# programmer.net
KiCad netlist of a schematic drawn in Altium Designer
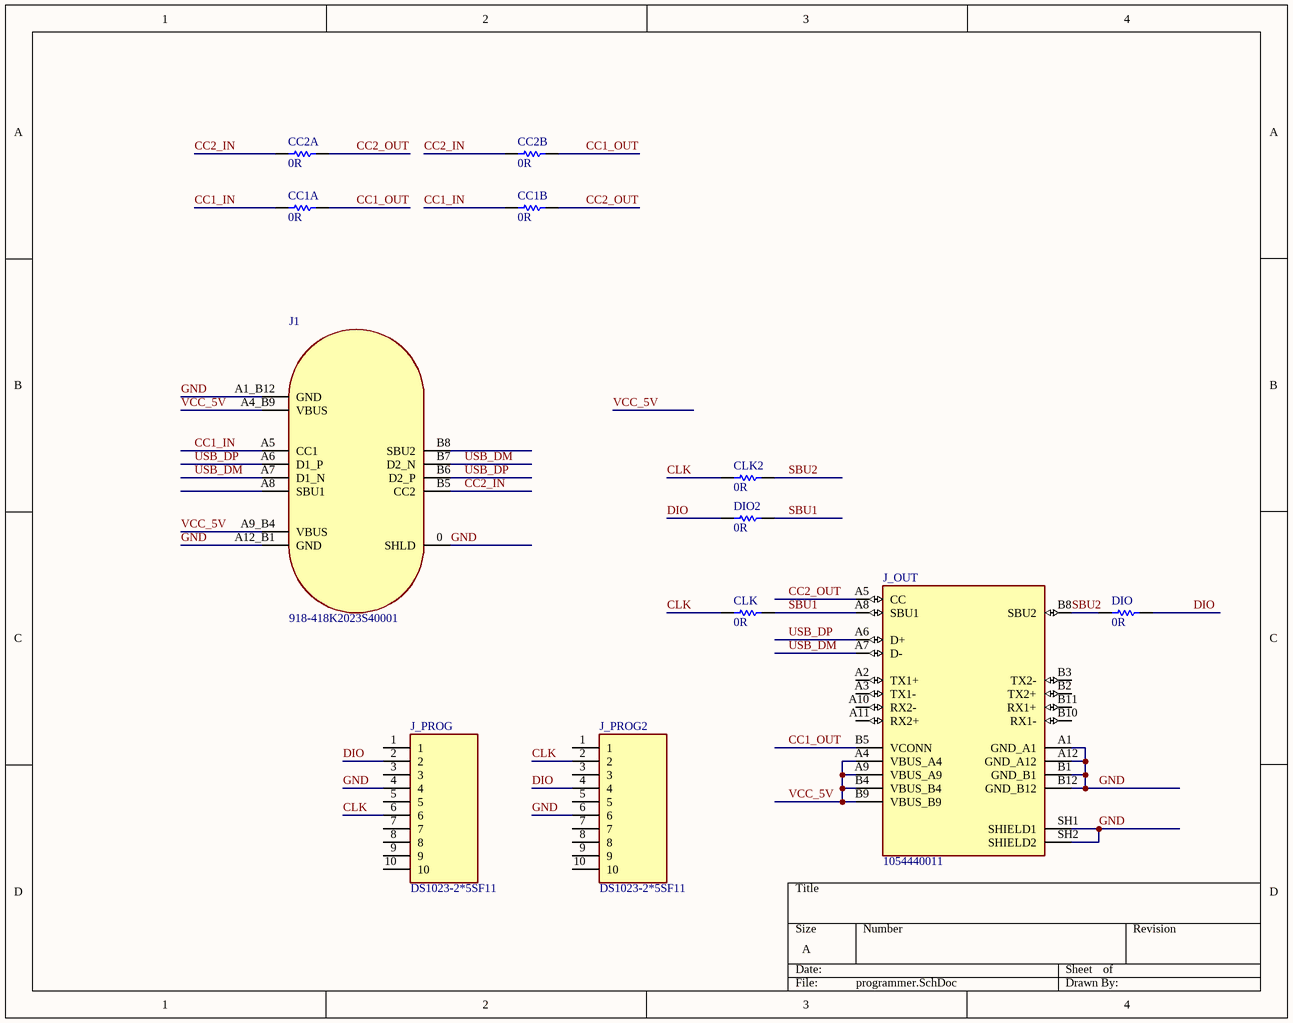
[diagram p0: programmer.SchDoc]

(export (version "E")
  (design (tool "Eeschema 10.0.6"))
  (components
    (comp (ref "CC1A")
      (value "0R")
      (footprint "R_0402")
      (description "R - RESISTOR - SMD - 0R - 1% - 0402")
      (fields (field (name "LCSC PART #") "C17168") (field (name "Comment") "0402WGF0000TCE"))
      (libsource (lib "JLC_PCB") (part "0402WGF0000TCE"))
    )
    (comp (ref "CC1B")
      (value "0R")
      (footprint "R_0402")
      (description "R - RESISTOR - SMD - 0R - 1% - 0402")
      (fields (field (name "LCSC PART #") "C17168") (field (name "Comment") "0402WGF0000TCE"))
      (libsource (lib "JLC_PCB") (part "0402WGF0000TCE"))
    )
    (comp (ref "CC2A")
      (value "0R")
      (footprint "R_0402")
      (description "R - RESISTOR - SMD - 0R - 1% - 0402")
      (fields (field (name "LCSC PART #") "C17168") (field (name "Comment") "0402WGF0000TCE"))
      (libsource (lib "JLC_PCB") (part "0402WGF0000TCE"))
    )
    (comp (ref "CC2B")
      (value "0R")
      (footprint "R_0402")
      (description "R - RESISTOR - SMD - 0R - 1% - 0402")
      (fields (field (name "LCSC PART #") "C17168") (field (name "Comment") "0402WGF0000TCE"))
      (libsource (lib "JLC_PCB") (part "0402WGF0000TCE"))
    )
    (comp (ref "CLK")
      (value "0R")
      (footprint "R_0402")
      (description "R - RESISTOR - SMD - 0R - 1% - 0402")
      (fields (field (name "LCSC PART #") "C17168") (field (name "Comment") "0402WGF0000TCE"))
      (libsource (lib "JLC_PCB") (part "0402WGF0000TCE"))
    )
    (comp (ref "CLK2")
      (value "0R")
      (footprint "R_0402")
      (description "R - RESISTOR - SMD - 0R - 1% - 0402")
      (fields (field (name "LCSC PART #") "C17168") (field (name "Comment") "0402WGF0000TCE"))
      (libsource (lib "JLC_PCB") (part "0402WGF0000TCE"))
    )
    (comp (ref "DIO")
      (value "0R")
      (footprint "R_0402")
      (description "R - RESISTOR - SMD - 0R - 1% - 0402")
      (fields (field (name "LCSC PART #") "C17168") (field (name "Comment") "0402WGF0000TCE"))
      (libsource (lib "JLC_PCB") (part "0402WGF0000TCE"))
    )
    (comp (ref "DIO2")
      (value "0R")
      (footprint "R_0402")
      (description "R - RESISTOR - SMD - 0R - 1% - 0402")
      (fields (field (name "LCSC PART #") "C17168") (field (name "Comment") "0402WGF0000TCE"))
      (libsource (lib "JLC_PCB") (part "0402WGF0000TCE"))
    )
    (comp (ref "J1")
      (value "918-418K2023S40001")
      (footprint "918-418K2023S40001")
      (description "J - JACK - USB - Type C - Recepticle - SMT - 90°")
      (fields (field (name "LCSC PART #") "C167321"))
      (libsource (lib "JLC_PCB") (part "918-418K2023S40001"))
    )
    (comp (ref "J_OUT")
      (value "1054440011")
      (footprint "MOLEX_1054440011")
      (fields (field (name "LCSC PART #") "C561769") (field (name "MF") "Molex"))
      (libsource (lib "JLC_PCB") (part "1054440011"))
    )
    (comp (ref "J_PROG")
      (value "DS1023-2*5SF11")
      (footprint "HDR_FEM_2X5P")
      (description "J - JACK - PIN_HEADER 2X5P")
      (fields (field (name "LCSC PART #") "C92270"))
      (libsource (lib "JLC_PCB") (part "DS1023-2*5SF11"))
    )
    (comp (ref "J_PROG2")
      (value "DS1023-2*5SF11")
      (footprint "HDR_FEM_2X5P")
      (description "J - JACK - PIN_HEADER 2X5P")
      (fields (field (name "LCSC PART #") "C92270"))
      (libsource (lib "JLC_PCB") (part "DS1023-2*5SF11"))
    )
  )
  (nets
    (net (code "1") (name "/CC1_IN") (class "Default")
      (node (ref "CC1A") (pin "1") (pinfunction "1_1") (pintype "passive"))
      (node (ref "CC1B") (pin "1") (pinfunction "1_1") (pintype "passive"))
      (node (ref "J1") (pin "A5") (pinfunction "CC1_A5") (pintype "passive"))
    )
    (net (code "2") (name "/CC1_OUT") (class "Default")
      (node (ref "CC1A") (pin "2") (pinfunction "2_2") (pintype "passive"))
      (node (ref "CC2B") (pin "2") (pinfunction "2_2") (pintype "passive"))
      (node (ref "J_OUT") (pin "B5") (pinfunction "VCONN_B5") (pintype "power_in"))
    )
    (net (code "3") (name "/CC2_IN") (class "Default")
      (node (ref "CC2A") (pin "1") (pinfunction "1_1") (pintype "passive"))
      (node (ref "CC2B") (pin "1") (pinfunction "1_1") (pintype "passive"))
      (node (ref "J1") (pin "B5") (pinfunction "CC2_B5") (pintype "passive"))
    )
    (net (code "4") (name "/CC2_OUT") (class "Default")
      (node (ref "CC1B") (pin "2") (pinfunction "2_2") (pintype "passive"))
      (node (ref "CC2A") (pin "2") (pinfunction "2_2") (pintype "passive"))
      (node (ref "J_OUT") (pin "A5") (pinfunction "CC_A5") (pintype "bidirectional"))
    )
    (net (code "5") (name "/CLK") (class "Default")
      (node (ref "CLK") (pin "1") (pinfunction "1_1") (pintype "passive"))
      (node (ref "CLK2") (pin "1") (pinfunction "1_1") (pintype "passive"))
      (node (ref "J_PROG") (pin "6") (pinfunction "6_6") (pintype "passive"))
      (node (ref "J_PROG2") (pin "2") (pinfunction "2_2") (pintype "passive"))
    )
    (net (code "6") (name "/DIO") (class "Default")
      (node (ref "DIO") (pin "2") (pinfunction "2_2") (pintype "passive"))
      (node (ref "DIO2") (pin "1") (pinfunction "1_1") (pintype "passive"))
      (node (ref "J_PROG") (pin "2") (pinfunction "2_2") (pintype "passive"))
      (node (ref "J_PROG2") (pin "4") (pinfunction "4_4") (pintype "passive"))
    )
    (net (code "7") (name "/GND") (class "Default")
      (node (ref "J1") (pin "0") (pinfunction "SHLD_0") (pintype "passive"))
      (node (ref "J1") (pin "A12_B1") (pinfunction "GND_A12_B1") (pintype "passive"))
      (node (ref "J1") (pin "A1_B12") (pinfunction "GND_A1_B12") (pintype "passive"))
      (node (ref "J_OUT") (pin "A1") (pinfunction "GND_A1_A1") (pintype "power_in"))
      (node (ref "J_OUT") (pin "A12") (pinfunction "GND_A12_A12") (pintype "power_in"))
      (node (ref "J_OUT") (pin "B1") (pinfunction "GND_B1_B1") (pintype "power_in"))
      (node (ref "J_OUT") (pin "B12") (pinfunction "GND_B12_B12") (pintype "power_in"))
      (node (ref "J_OUT") (pin "SH1") (pinfunction "SHIELD1_SH1") (pintype "passive"))
      (node (ref "J_OUT") (pin "SH2") (pinfunction "SHIELD2_SH2") (pintype "passive"))
      (node (ref "J_PROG") (pin "4") (pinfunction "4_4") (pintype "passive"))
      (node (ref "J_PROG2") (pin "6") (pinfunction "6_6") (pintype "passive"))
    )
    (net (code "8") (name "/SBU1") (class "Default")
      (node (ref "CLK") (pin "2") (pinfunction "2_2") (pintype "passive"))
      (node (ref "DIO2") (pin "2") (pinfunction "2_2") (pintype "passive"))
      (node (ref "J_OUT") (pin "A8") (pinfunction "SBU1_A8") (pintype "bidirectional"))
    )
    (net (code "9") (name "/SBU2") (class "Default")
      (node (ref "CLK2") (pin "2") (pinfunction "2_2") (pintype "passive"))
      (node (ref "DIO") (pin "1") (pinfunction "1_1") (pintype "passive"))
      (node (ref "J_OUT") (pin "B8") (pinfunction "SBU2_B8") (pintype "bidirectional"))
    )
    (net (code "10") (name "/USB_DM") (class "Default")
      (node (ref "J1") (pin "A7") (pinfunction "D1_N_A7") (pintype "passive"))
      (node (ref "J1") (pin "B7") (pinfunction "D2_N_B7") (pintype "passive"))
      (node (ref "J_OUT") (pin "A7") (pinfunction "D-_A7") (pintype "bidirectional"))
    )
    (net (code "11") (name "/USB_DP") (class "Default")
      (node (ref "J1") (pin "A6") (pinfunction "D1_P_A6") (pintype "passive"))
      (node (ref "J1") (pin "B6") (pinfunction "D2_P_B6") (pintype "passive"))
      (node (ref "J_OUT") (pin "A6") (pinfunction "D+_A6") (pintype "bidirectional"))
    )
    (net (code "12") (name "/VCC_5V") (class "Default")
      (node (ref "J1") (pin "A4_B9") (pinfunction "VBUS_A4_B9") (pintype "power_in"))
      (node (ref "J1") (pin "A9_B4") (pinfunction "VBUS_A9_B4") (pintype "power_in"))
      (node (ref "J_OUT") (pin "A4") (pinfunction "VBUS_A4_A4") (pintype "power_in"))
      (node (ref "J_OUT") (pin "A9") (pinfunction "VBUS_A9_A9") (pintype "power_in"))
      (node (ref "J_OUT") (pin "B4") (pinfunction "VBUS_B4_B4") (pintype "power_in"))
      (node (ref "J_OUT") (pin "B9") (pinfunction "VBUS_B9_B9") (pintype "power_in"))
    )
    (net (code "13") (name "unconnected-(J1-SBU1-PadA8)") (class "Default")
      (node (ref "J1") (pin "A8") (pinfunction "SBU1_A8") (pintype "passive"))
    )
    (net (code "14") (name "unconnected-(J1-SBU2-PadB8)") (class "Default")
      (node (ref "J1") (pin "B8") (pinfunction "SBU2_B8") (pintype "passive"))
    )
    (net (code "15") (name "unconnected-(J_OUT-RX1+-PadB11)") (class "Default")
      (node (ref "J_OUT") (pin "B11") (pinfunction "RX1+_B11") (pintype "bidirectional"))
    )
    (net (code "16") (name "unconnected-(J_OUT-RX1--PadB10)") (class "Default")
      (node (ref "J_OUT") (pin "B10") (pinfunction "RX1-_B10") (pintype "bidirectional"))
    )
    (net (code "17") (name "unconnected-(J_OUT-RX2+-PadA11)") (class "Default")
      (node (ref "J_OUT") (pin "A11") (pinfunction "RX2+_A11") (pintype "bidirectional"))
    )
    (net (code "18") (name "unconnected-(J_OUT-RX2--PadA10)") (class "Default")
      (node (ref "J_OUT") (pin "A10") (pinfunction "RX2-_A10") (pintype "bidirectional"))
    )
    (net (code "19") (name "unconnected-(J_OUT-TX1+-PadA2)") (class "Default")
      (node (ref "J_OUT") (pin "A2") (pinfunction "TX1+_A2") (pintype "bidirectional"))
    )
    (net (code "20") (name "unconnected-(J_OUT-TX1--PadA3)") (class "Default")
      (node (ref "J_OUT") (pin "A3") (pinfunction "TX1-_A3") (pintype "bidirectional"))
    )
    (net (code "21") (name "unconnected-(J_OUT-TX2+-PadB2)") (class "Default")
      (node (ref "J_OUT") (pin "B2") (pinfunction "TX2+_B2") (pintype "bidirectional"))
    )
    (net (code "22") (name "unconnected-(J_OUT-TX2--PadB3)") (class "Default")
      (node (ref "J_OUT") (pin "B3") (pinfunction "TX2-_B3") (pintype "bidirectional"))
    )
    (net (code "23") (name "unconnected-(J_PROG-Pad1)") (class "Default")
      (node (ref "J_PROG") (pin "1") (pinfunction "1_1") (pintype "passive"))
    )
    (net (code "24") (name "unconnected-(J_PROG-Pad3)") (class "Default")
      (node (ref "J_PROG") (pin "3") (pinfunction "3_3") (pintype "passive"))
    )
    (net (code "25") (name "unconnected-(J_PROG-Pad5)") (class "Default")
      (node (ref "J_PROG") (pin "5") (pinfunction "5_5") (pintype "passive"))
    )
    (net (code "26") (name "unconnected-(J_PROG-Pad7)") (class "Default")
      (node (ref "J_PROG") (pin "7") (pinfunction "7_7") (pintype "passive"))
    )
    (net (code "27") (name "unconnected-(J_PROG-Pad8)") (class "Default")
      (node (ref "J_PROG") (pin "8") (pinfunction "8_8") (pintype "passive"))
    )
    (net (code "28") (name "unconnected-(J_PROG-Pad9)") (class "Default")
      (node (ref "J_PROG") (pin "9") (pinfunction "9_9") (pintype "passive"))
    )
    (net (code "29") (name "unconnected-(J_PROG-Pad10)") (class "Default")
      (node (ref "J_PROG") (pin "10") (pinfunction "10_10") (pintype "passive"))
    )
    (net (code "30") (name "unconnected-(J_PROG2-Pad1)") (class "Default")
      (node (ref "J_PROG2") (pin "1") (pinfunction "1_1") (pintype "passive"))
    )
    (net (code "31") (name "unconnected-(J_PROG2-Pad3)") (class "Default")
      (node (ref "J_PROG2") (pin "3") (pinfunction "3_3") (pintype "passive"))
    )
    (net (code "32") (name "unconnected-(J_PROG2-Pad5)") (class "Default")
      (node (ref "J_PROG2") (pin "5") (pinfunction "5_5") (pintype "passive"))
    )
    (net (code "33") (name "unconnected-(J_PROG2-Pad7)") (class "Default")
      (node (ref "J_PROG2") (pin "7") (pinfunction "7_7") (pintype "passive"))
    )
    (net (code "34") (name "unconnected-(J_PROG2-Pad8)") (class "Default")
      (node (ref "J_PROG2") (pin "8") (pinfunction "8_8") (pintype "passive"))
    )
    (net (code "35") (name "unconnected-(J_PROG2-Pad9)") (class "Default")
      (node (ref "J_PROG2") (pin "9") (pinfunction "9_9") (pintype "passive"))
    )
    (net (code "36") (name "unconnected-(J_PROG2-Pad10)") (class "Default")
      (node (ref "J_PROG2") (pin "10") (pinfunction "10_10") (pintype "passive"))
    )
  )
)
